# ezo_probe_expansion_1.net
KiCad netlist of a schematic drawn in EAGLE
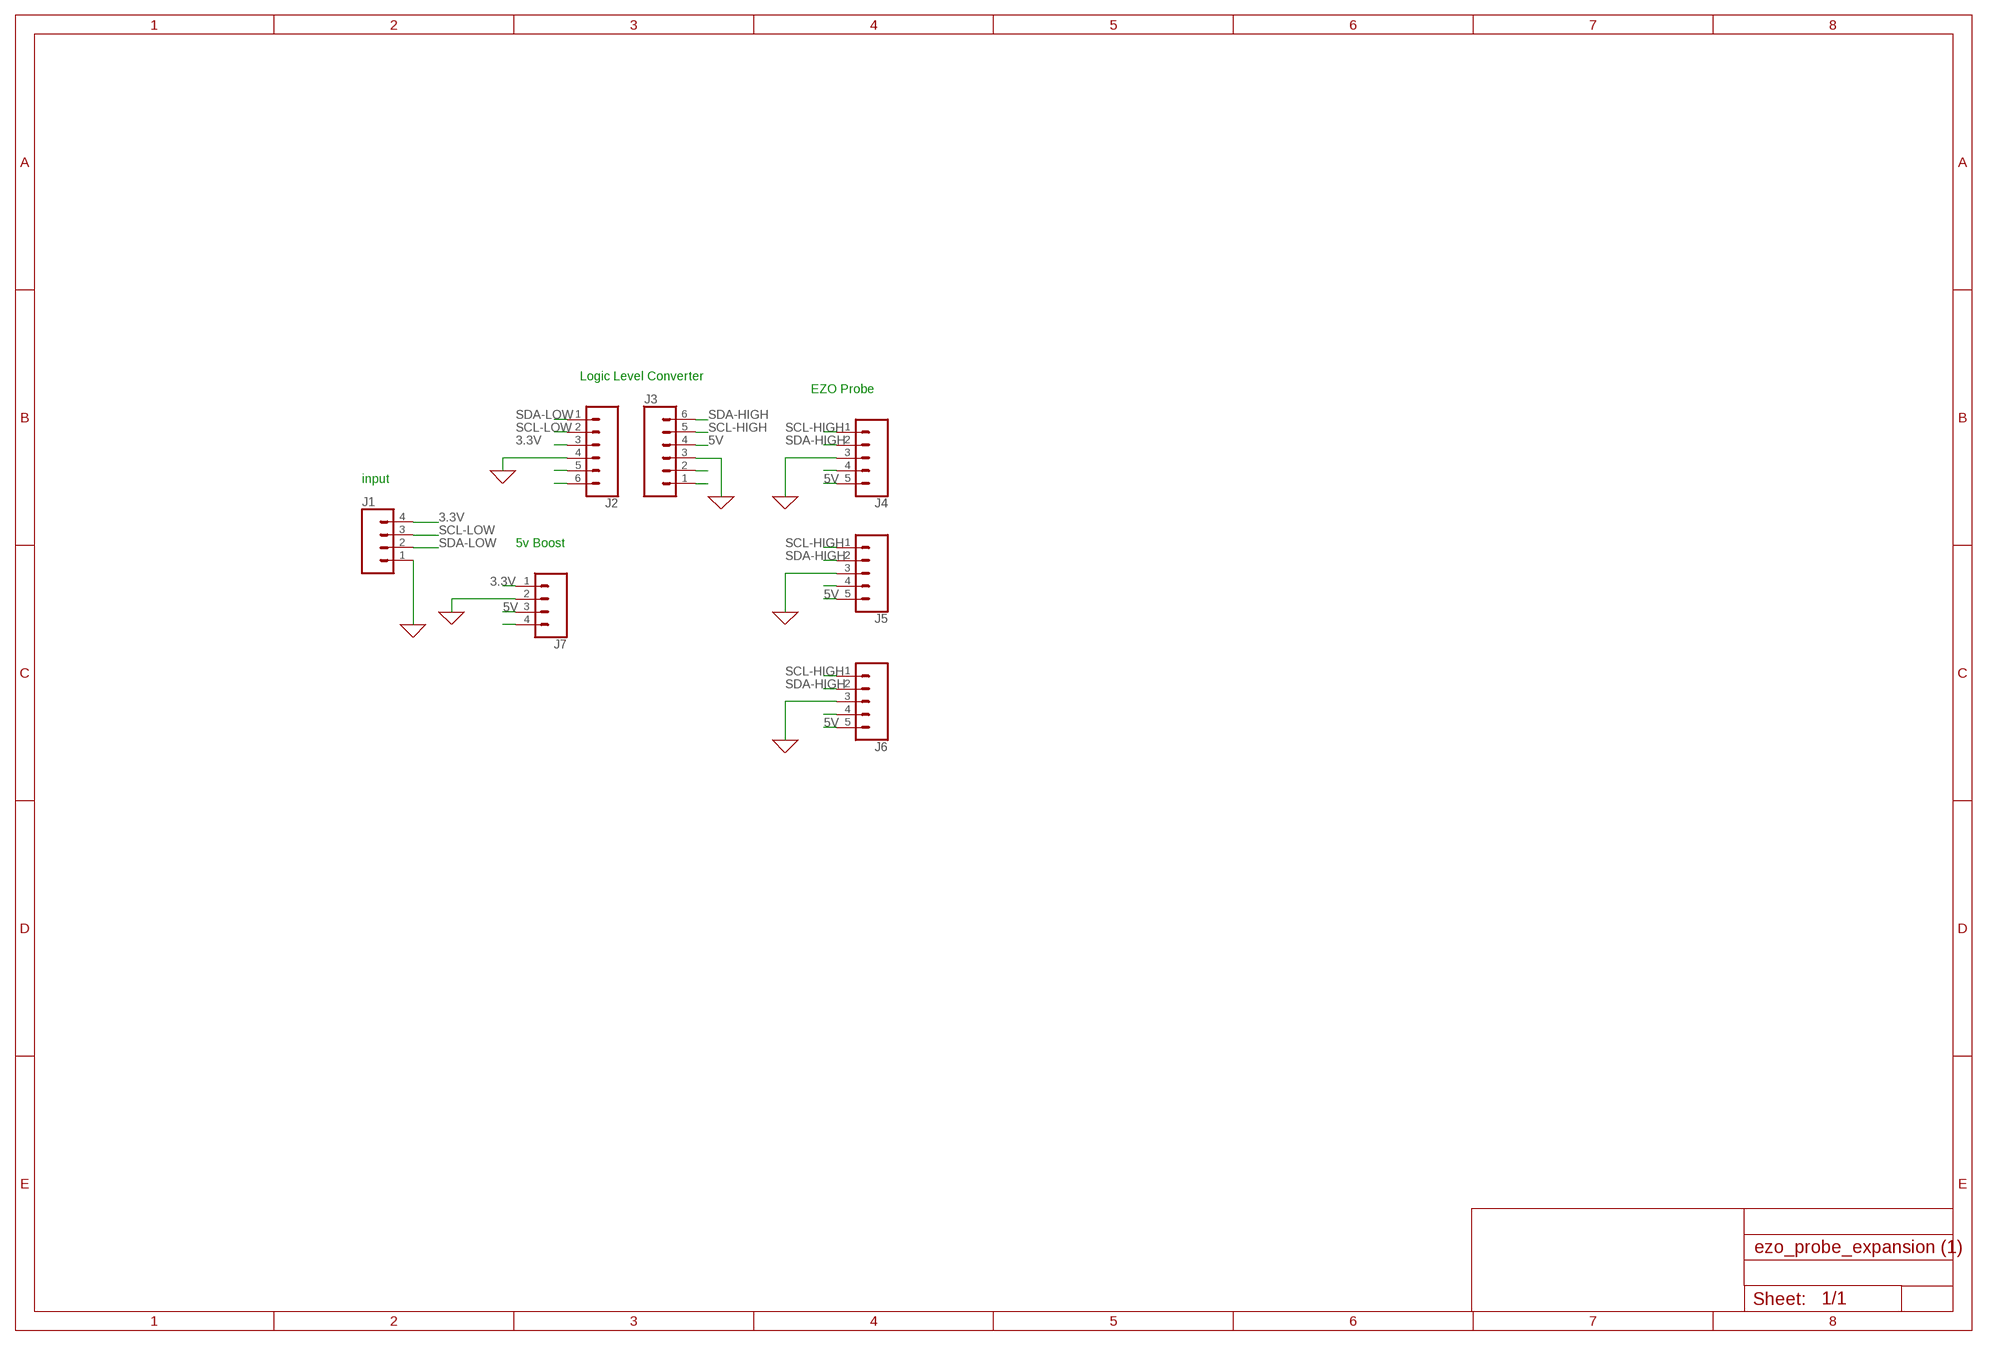
[diagram p0: schematic, sheet 1]

(export (version "E")
  (design (tool "Eeschema 10.0.6"))
  (components
    (comp (ref "J1")
      (value "CONN_04PTH")
      (footprint "eagle-import:1X04")
      (libsource (lib "eagle-import") (part "CONN_04PTH"))
    )
    (comp (ref "J2")
      (value "CONN_06SILK_FEMALE_PTH")
      (footprint "eagle-import:1X06")
      (libsource (lib "eagle-import") (part "CONN_06SILK_FEMALE_PTH"))
    )
    (comp (ref "J3")
      (value "CONN_06SILK_FEMALE_PTH")
      (footprint "eagle-import:1X06")
      (libsource (lib "eagle-import") (part "CONN_06SILK_FEMALE_PTH"))
    )
    (comp (ref "J4")
      (value "CONN_05PTH")
      (footprint "eagle-import:1X05")
      (libsource (lib "eagle-import") (part "CONN_05PTH"))
    )
    (comp (ref "J5")
      (value "CONN_05PTH")
      (footprint "eagle-import:1X05")
      (libsource (lib "eagle-import") (part "CONN_05PTH"))
    )
    (comp (ref "J6")
      (value "CONN_05PTH")
      (footprint "eagle-import:1X05")
      (libsource (lib "eagle-import") (part "CONN_05PTH"))
    )
    (comp (ref "J7")
      (value "CONN_04PTH")
      (footprint "eagle-import:1X04")
      (libsource (lib "eagle-import") (part "CONN_04PTH"))
    )
  )
  (nets
    (net (code "1") (name "/3.3V") (class "Default")
      (node (ref "J1") (pin "4") (pinfunction "4_4") (pintype "passive"))
      (node (ref "J2") (pin "3") (pinfunction "3_3") (pintype "passive"))
      (node (ref "J7") (pin "1") (pinfunction "1_1") (pintype "passive"))
    )
    (net (code "2") (name "/5V") (class "Default")
      (node (ref "J3") (pin "4") (pinfunction "4_4") (pintype "passive"))
      (node (ref "J4") (pin "5") (pinfunction "5_5") (pintype "passive"))
      (node (ref "J5") (pin "5") (pinfunction "5_5") (pintype "passive"))
      (node (ref "J6") (pin "5") (pinfunction "5_5") (pintype "passive"))
      (node (ref "J7") (pin "3") (pinfunction "3_3") (pintype "passive"))
    )
    (net (code "3") (name "/SCL-HIGH") (class "Default")
      (node (ref "J3") (pin "5") (pinfunction "5_5") (pintype "passive"))
      (node (ref "J4") (pin "1") (pinfunction "1_1") (pintype "passive"))
      (node (ref "J5") (pin "1") (pinfunction "1_1") (pintype "passive"))
      (node (ref "J6") (pin "1") (pinfunction "1_1") (pintype "passive"))
    )
    (net (code "4") (name "/SCL-LOW") (class "Default")
      (node (ref "J1") (pin "3") (pinfunction "3_3") (pintype "passive"))
      (node (ref "J2") (pin "2") (pinfunction "2_2") (pintype "passive"))
    )
    (net (code "5") (name "/SDA-HIGH") (class "Default")
      (node (ref "J3") (pin "6") (pinfunction "6_6") (pintype "passive"))
      (node (ref "J4") (pin "2") (pinfunction "2_2") (pintype "passive"))
      (node (ref "J5") (pin "2") (pinfunction "2_2") (pintype "passive"))
      (node (ref "J6") (pin "2") (pinfunction "2_2") (pintype "passive"))
    )
    (net (code "6") (name "/SDA-LOW") (class "Default")
      (node (ref "J1") (pin "2") (pinfunction "2_2") (pintype "passive"))
      (node (ref "J2") (pin "1") (pinfunction "1_1") (pintype "passive"))
    )
    (net (code "7") (name "GND") (class "Default")
      (node (ref "J1") (pin "1") (pinfunction "1_1") (pintype "passive"))
      (node (ref "J2") (pin "4") (pinfunction "4_4") (pintype "passive"))
      (node (ref "J3") (pin "3") (pinfunction "3_3") (pintype "passive"))
      (node (ref "J4") (pin "3") (pinfunction "3_3") (pintype "passive"))
      (node (ref "J5") (pin "3") (pinfunction "3_3") (pintype "passive"))
      (node (ref "J6") (pin "3") (pinfunction "3_3") (pintype "passive"))
      (node (ref "J7") (pin "2") (pinfunction "2_2") (pintype "passive"))
    )
    (net (code "8") (name "unconnected-(J2-Pad5)") (class "Default")
      (node (ref "J2") (pin "5") (pinfunction "5_5") (pintype "passive"))
    )
    (net (code "9") (name "unconnected-(J2-Pad6)") (class "Default")
      (node (ref "J2") (pin "6") (pinfunction "6_6") (pintype "passive"))
    )
    (net (code "10") (name "unconnected-(J3-Pad1)") (class "Default")
      (node (ref "J3") (pin "1") (pinfunction "1_1") (pintype "passive"))
    )
    (net (code "11") (name "unconnected-(J3-Pad2)") (class "Default")
      (node (ref "J3") (pin "2") (pinfunction "2_2") (pintype "passive"))
    )
    (net (code "12") (name "unconnected-(J4-Pad4)") (class "Default")
      (node (ref "J4") (pin "4") (pinfunction "4_4") (pintype "passive"))
    )
    (net (code "13") (name "unconnected-(J5-Pad4)") (class "Default")
      (node (ref "J5") (pin "4") (pinfunction "4_4") (pintype "passive"))
    )
    (net (code "14") (name "unconnected-(J6-Pad4)") (class "Default")
      (node (ref "J6") (pin "4") (pinfunction "4_4") (pintype "passive"))
    )
    (net (code "15") (name "unconnected-(J7-Pad4)") (class "Default")
      (node (ref "J7") (pin "4") (pinfunction "4_4") (pintype "passive"))
    )
  )
)
